# BandPassFilter.net
KiCad netlist of a schematic drawn in Altium Designer
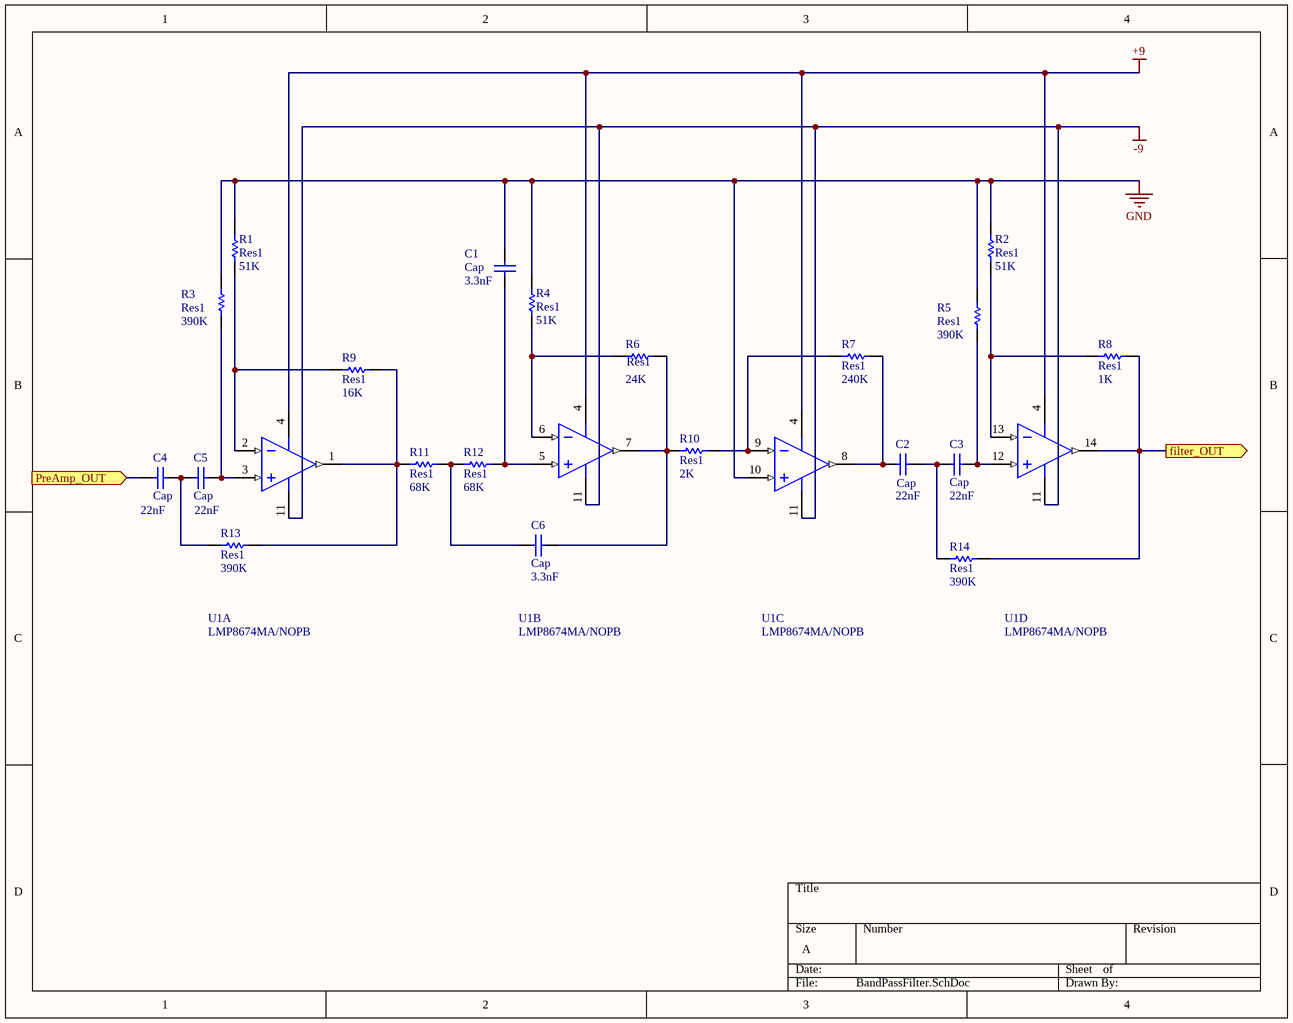
[diagram p0: BandPassFilter.SchDoc]

(export (version "E")
  (design (tool "Eeschema 10.0.6"))
  (components
    (comp (ref "C1")
      (value "Cap")
      (footprint "C0805")
      (description "Capacitor")
      (fields (field (name "ALTIUM_VALUE") "3.3nF") (field (name "PUBLISHER") "Altium Limited"))
      (libsource (lib "Miscellaneous Devices") (part "Cap"))
    )
    (comp (ref "C2")
      (value "Cap")
      (footprint "C0805")
      (description "Capacitor")
      (fields (field (name "ALTIUM_VALUE") "22nF") (field (name "PUBLISHER") "Altium Limited"))
      (libsource (lib "Miscellaneous Devices") (part "Cap"))
    )
    (comp (ref "C3")
      (value "Cap")
      (footprint "C0805")
      (description "Capacitor")
      (fields (field (name "ALTIUM_VALUE") "22nF") (field (name "PUBLISHER") "Altium Limited"))
      (libsource (lib "Miscellaneous Devices") (part "Cap"))
    )
    (comp (ref "C4")
      (value "Cap")
      (footprint "C0805")
      (description "Capacitor")
      (fields (field (name "ALTIUM_VALUE") "22nF") (field (name "PUBLISHER") "Altium Limited"))
      (libsource (lib "Miscellaneous Devices") (part "Cap"))
    )
    (comp (ref "C5")
      (value "Cap")
      (footprint "C0805")
      (description "Capacitor")
      (fields (field (name "ALTIUM_VALUE") "22nF") (field (name "PUBLISHER") "Altium Limited"))
      (libsource (lib "Miscellaneous Devices") (part "Cap"))
    )
    (comp (ref "C6")
      (value "Cap")
      (footprint "C0805")
      (description "Capacitor")
      (fields (field (name "ALTIUM_VALUE") "3.3nF") (field (name "PUBLISHER") "Altium Limited"))
      (libsource (lib "Miscellaneous Devices") (part "Cap"))
    )
    (comp (ref "R1")
      (value "Res1")
      (footprint "6-0805_L")
      (description "Resistor")
      (fields (field (name "ALTIUM_VALUE") "51K") (field (name "PUBLISHER") "Altium Limited"))
      (libsource (lib "Miscellaneous Devices") (part "Res1"))
    )
    (comp (ref "R2")
      (value "Res1")
      (footprint "6-0805_L")
      (description "Resistor")
      (fields (field (name "ALTIUM_VALUE") "51K") (field (name "PUBLISHER") "Altium Limited"))
      (libsource (lib "Miscellaneous Devices") (part "Res1"))
    )
    (comp (ref "R3")
      (value "Res1")
      (footprint "6-0805_L")
      (description "Resistor")
      (fields (field (name "ALTIUM_VALUE") "390K") (field (name "PUBLISHER") "Altium Limited"))
      (libsource (lib "Miscellaneous Devices") (part "Res1"))
    )
    (comp (ref "R4")
      (value "Res1")
      (footprint "6-0805_L")
      (description "Resistor")
      (fields (field (name "ALTIUM_VALUE") "51K") (field (name "PUBLISHER") "Altium Limited"))
      (libsource (lib "Miscellaneous Devices") (part "Res1"))
    )
    (comp (ref "R5")
      (value "Res1")
      (footprint "6-0805_L")
      (description "Resistor")
      (fields (field (name "ALTIUM_VALUE") "390K") (field (name "PUBLISHER") "Altium Limited"))
      (libsource (lib "Miscellaneous Devices") (part "Res1"))
    )
    (comp (ref "R6")
      (value "Res1")
      (footprint "6-0805_L")
      (description "Resistor")
      (fields (field (name "ALTIUM_VALUE") "24K") (field (name "PUBLISHER") "Altium Limited"))
      (libsource (lib "Miscellaneous Devices") (part "Res1"))
    )
    (comp (ref "R7")
      (value "Res1")
      (footprint "6-0805_L")
      (description "Resistor")
      (fields (field (name "ALTIUM_VALUE") "240K") (field (name "PUBLISHER") "Altium Limited"))
      (libsource (lib "Miscellaneous Devices") (part "Res1"))
    )
    (comp (ref "R8")
      (value "Res1")
      (footprint "6-0805_L")
      (description "Resistor")
      (fields (field (name "ALTIUM_VALUE") "1K") (field (name "PUBLISHER") "Altium Limited"))
      (libsource (lib "Miscellaneous Devices") (part "Res1"))
    )
    (comp (ref "R9")
      (value "Res1")
      (footprint "6-0805_L")
      (description "Resistor")
      (fields (field (name "ALTIUM_VALUE") "16K") (field (name "PUBLISHER") "Altium Limited"))
      (libsource (lib "Miscellaneous Devices") (part "Res1"))
    )
    (comp (ref "R10")
      (value "Res1")
      (footprint "6-0805_L")
      (description "Resistor")
      (fields (field (name "ALTIUM_VALUE") "2K") (field (name "PUBLISHER") "Altium Limited"))
      (libsource (lib "Miscellaneous Devices") (part "Res1"))
    )
    (comp (ref "R11")
      (value "Res1")
      (footprint "6-0805_L")
      (description "Resistor")
      (fields (field (name "ALTIUM_VALUE") "68K") (field (name "PUBLISHER") "Altium Limited"))
      (libsource (lib "Miscellaneous Devices") (part "Res1"))
    )
    (comp (ref "R12")
      (value "Res1")
      (footprint "6-0805_L")
      (description "Resistor")
      (fields (field (name "ALTIUM_VALUE") "68K") (field (name "PUBLISHER") "Altium Limited"))
      (libsource (lib "Miscellaneous Devices") (part "Res1"))
    )
    (comp (ref "R13")
      (value "Res1")
      (footprint "6-0805_L")
      (description "Resistor")
      (fields (field (name "ALTIUM_VALUE") "390K") (field (name "PUBLISHER") "Altium Limited"))
      (libsource (lib "Miscellaneous Devices") (part "Res1"))
    )
    (comp (ref "R14")
      (value "Res1")
      (footprint "6-0805_L")
      (description "Resistor")
      (fields (field (name "ALTIUM_VALUE") "390K") (field (name "PUBLISHER") "Altium Limited"))
      (libsource (lib "Miscellaneous Devices") (part "Res1"))
    )
    (comp (ref "U1")
      (value "LMP8674MA/NOPB")
      (footprint "M14A_N")
      (description "Quad 40V Low Noise Precision Amplifier, 14-pin Narrow SOIC, 55 Rail")
      (fields (field (name "MANUFACTURER") "National Semiconductor"))
      (libsource (lib "National Semiconductor Amplifier") (part "LMP8674MA/NOPB"))
    )
  )
  (nets
    (net (code "1") (name "+9") (class "Default")
      (node (ref "U1") (pin "4") (pinfunction "V+_4") (pintype "power_in"))
    )
    (net (code "2") (name "-9") (class "Default")
      (node (ref "U1") (pin "11") (pinfunction "V-_11") (pintype "power_in"))
    )
    (net (code "3") (name "/PreAmp_OUT") (class "Default")
      (node (ref "C4") (pin "2") (pinfunction "2_2") (pintype "passive"))
    )
    (net (code "4") (name "/filter_OUT") (class "Default")
      (node (ref "R14") (pin "1") (pinfunction "1_1") (pintype "passive"))
      (node (ref "R8") (pin "1") (pinfunction "1_1") (pintype "passive"))
      (node (ref "U1") (pin "14") (pinfunction "OUT4_14") (pintype "output"))
    )
    (net (code "5") (name "GND") (class "Default")
      (node (ref "C1") (pin "1") (pinfunction "1_1") (pintype "passive"))
      (node (ref "R1") (pin "2") (pinfunction "2_2") (pintype "passive"))
      (node (ref "R2") (pin "2") (pinfunction "2_2") (pintype "passive"))
      (node (ref "R3") (pin "2") (pinfunction "2_2") (pintype "passive"))
      (node (ref "R4") (pin "1") (pinfunction "1_1") (pintype "passive"))
      (node (ref "R5") (pin "2") (pinfunction "2_2") (pintype "passive"))
      (node (ref "U1") (pin "10") (pinfunction "IN3+_10") (pintype "input"))
    )
    (net (code "6") (name "Net-(C2-Pad2)") (class "Default")
      (node (ref "C2") (pin "2") (pinfunction "2_2") (pintype "passive"))
      (node (ref "C3") (pin "1") (pinfunction "1_1") (pintype "passive"))
      (node (ref "R14") (pin "2") (pinfunction "2_2") (pintype "passive"))
    )
    (net (code "7") (name "Net-(C4-Pad1)") (class "Default")
      (node (ref "C4") (pin "1") (pinfunction "1_1") (pintype "passive"))
      (node (ref "C5") (pin "2") (pinfunction "2_2") (pintype "passive"))
      (node (ref "R13") (pin "1") (pinfunction "1_1") (pintype "passive"))
    )
    (net (code "8") (name "Net-(C6-Pad2)") (class "Default")
      (node (ref "C6") (pin "2") (pinfunction "2_2") (pintype "passive"))
      (node (ref "R11") (pin "1") (pinfunction "1_1") (pintype "passive"))
      (node (ref "R12") (pin "2") (pinfunction "2_2") (pintype "passive"))
    )
    (net (code "9") (name "Net-(U1A-IN1+)") (class "Default")
      (node (ref "C5") (pin "1") (pinfunction "1_1") (pintype "passive"))
      (node (ref "R3") (pin "1") (pinfunction "1_1") (pintype "passive"))
      (node (ref "U1") (pin "3") (pinfunction "IN1+_3") (pintype "input"))
    )
    (net (code "10") (name "Net-(U1A-IN1-)") (class "Default")
      (node (ref "R1") (pin "1") (pinfunction "1_1") (pintype "passive"))
      (node (ref "R9") (pin "1") (pinfunction "1_1") (pintype "passive"))
      (node (ref "U1") (pin "2") (pinfunction "IN1-_2") (pintype "input"))
    )
    (net (code "11") (name "Net-(U1A-OUT1)") (class "Default")
      (node (ref "R11") (pin "2") (pinfunction "2_2") (pintype "passive"))
      (node (ref "R13") (pin "2") (pinfunction "2_2") (pintype "passive"))
      (node (ref "R9") (pin "2") (pinfunction "2_2") (pintype "passive"))
      (node (ref "U1") (pin "1") (pinfunction "OUT1_1") (pintype "output"))
    )
    (net (code "12") (name "Net-(U1B-IN2+)") (class "Default")
      (node (ref "C1") (pin "2") (pinfunction "2_2") (pintype "passive"))
      (node (ref "R12") (pin "1") (pinfunction "1_1") (pintype "passive"))
      (node (ref "U1") (pin "5") (pinfunction "IN2+_5") (pintype "input"))
    )
    (net (code "13") (name "Net-(U1B-IN2-)") (class "Default")
      (node (ref "R4") (pin "2") (pinfunction "2_2") (pintype "passive"))
      (node (ref "R6") (pin "1") (pinfunction "1_1") (pintype "passive"))
      (node (ref "U1") (pin "6") (pinfunction "IN2-_6") (pintype "input"))
    )
    (net (code "14") (name "Net-(U1B-OUT2)") (class "Default")
      (node (ref "C6") (pin "1") (pinfunction "1_1") (pintype "passive"))
      (node (ref "R10") (pin "1") (pinfunction "1_1") (pintype "passive"))
      (node (ref "R6") (pin "2") (pinfunction "2_2") (pintype "passive"))
      (node (ref "U1") (pin "7") (pinfunction "OUT2_7") (pintype "output"))
    )
    (net (code "15") (name "Net-(U1C-IN3-)") (class "Default")
      (node (ref "R10") (pin "2") (pinfunction "2_2") (pintype "passive"))
      (node (ref "R7") (pin "1") (pinfunction "1_1") (pintype "passive"))
      (node (ref "U1") (pin "9") (pinfunction "IN3-_9") (pintype "input"))
    )
    (net (code "16") (name "Net-(U1C-OUT3)") (class "Default")
      (node (ref "C2") (pin "1") (pinfunction "1_1") (pintype "passive"))
      (node (ref "R7") (pin "2") (pinfunction "2_2") (pintype "passive"))
      (node (ref "U1") (pin "8") (pinfunction "OUT3_8") (pintype "output"))
    )
    (net (code "17") (name "Net-(U1D-IN4+)") (class "Default")
      (node (ref "C3") (pin "2") (pinfunction "2_2") (pintype "passive"))
      (node (ref "R5") (pin "1") (pinfunction "1_1") (pintype "passive"))
      (node (ref "U1") (pin "12") (pinfunction "IN4+_12") (pintype "input"))
    )
    (net (code "18") (name "Net-(U1D-IN4-)") (class "Default")
      (node (ref "R2") (pin "1") (pinfunction "1_1") (pintype "passive"))
      (node (ref "R8") (pin "2") (pinfunction "2_2") (pintype "passive"))
      (node (ref "U1") (pin "13") (pinfunction "IN4-_13") (pintype "input"))
    )
  )
)
